# 06_LMS7002M_Power.net
KiCad netlist of a schematic drawn in Altium Designer
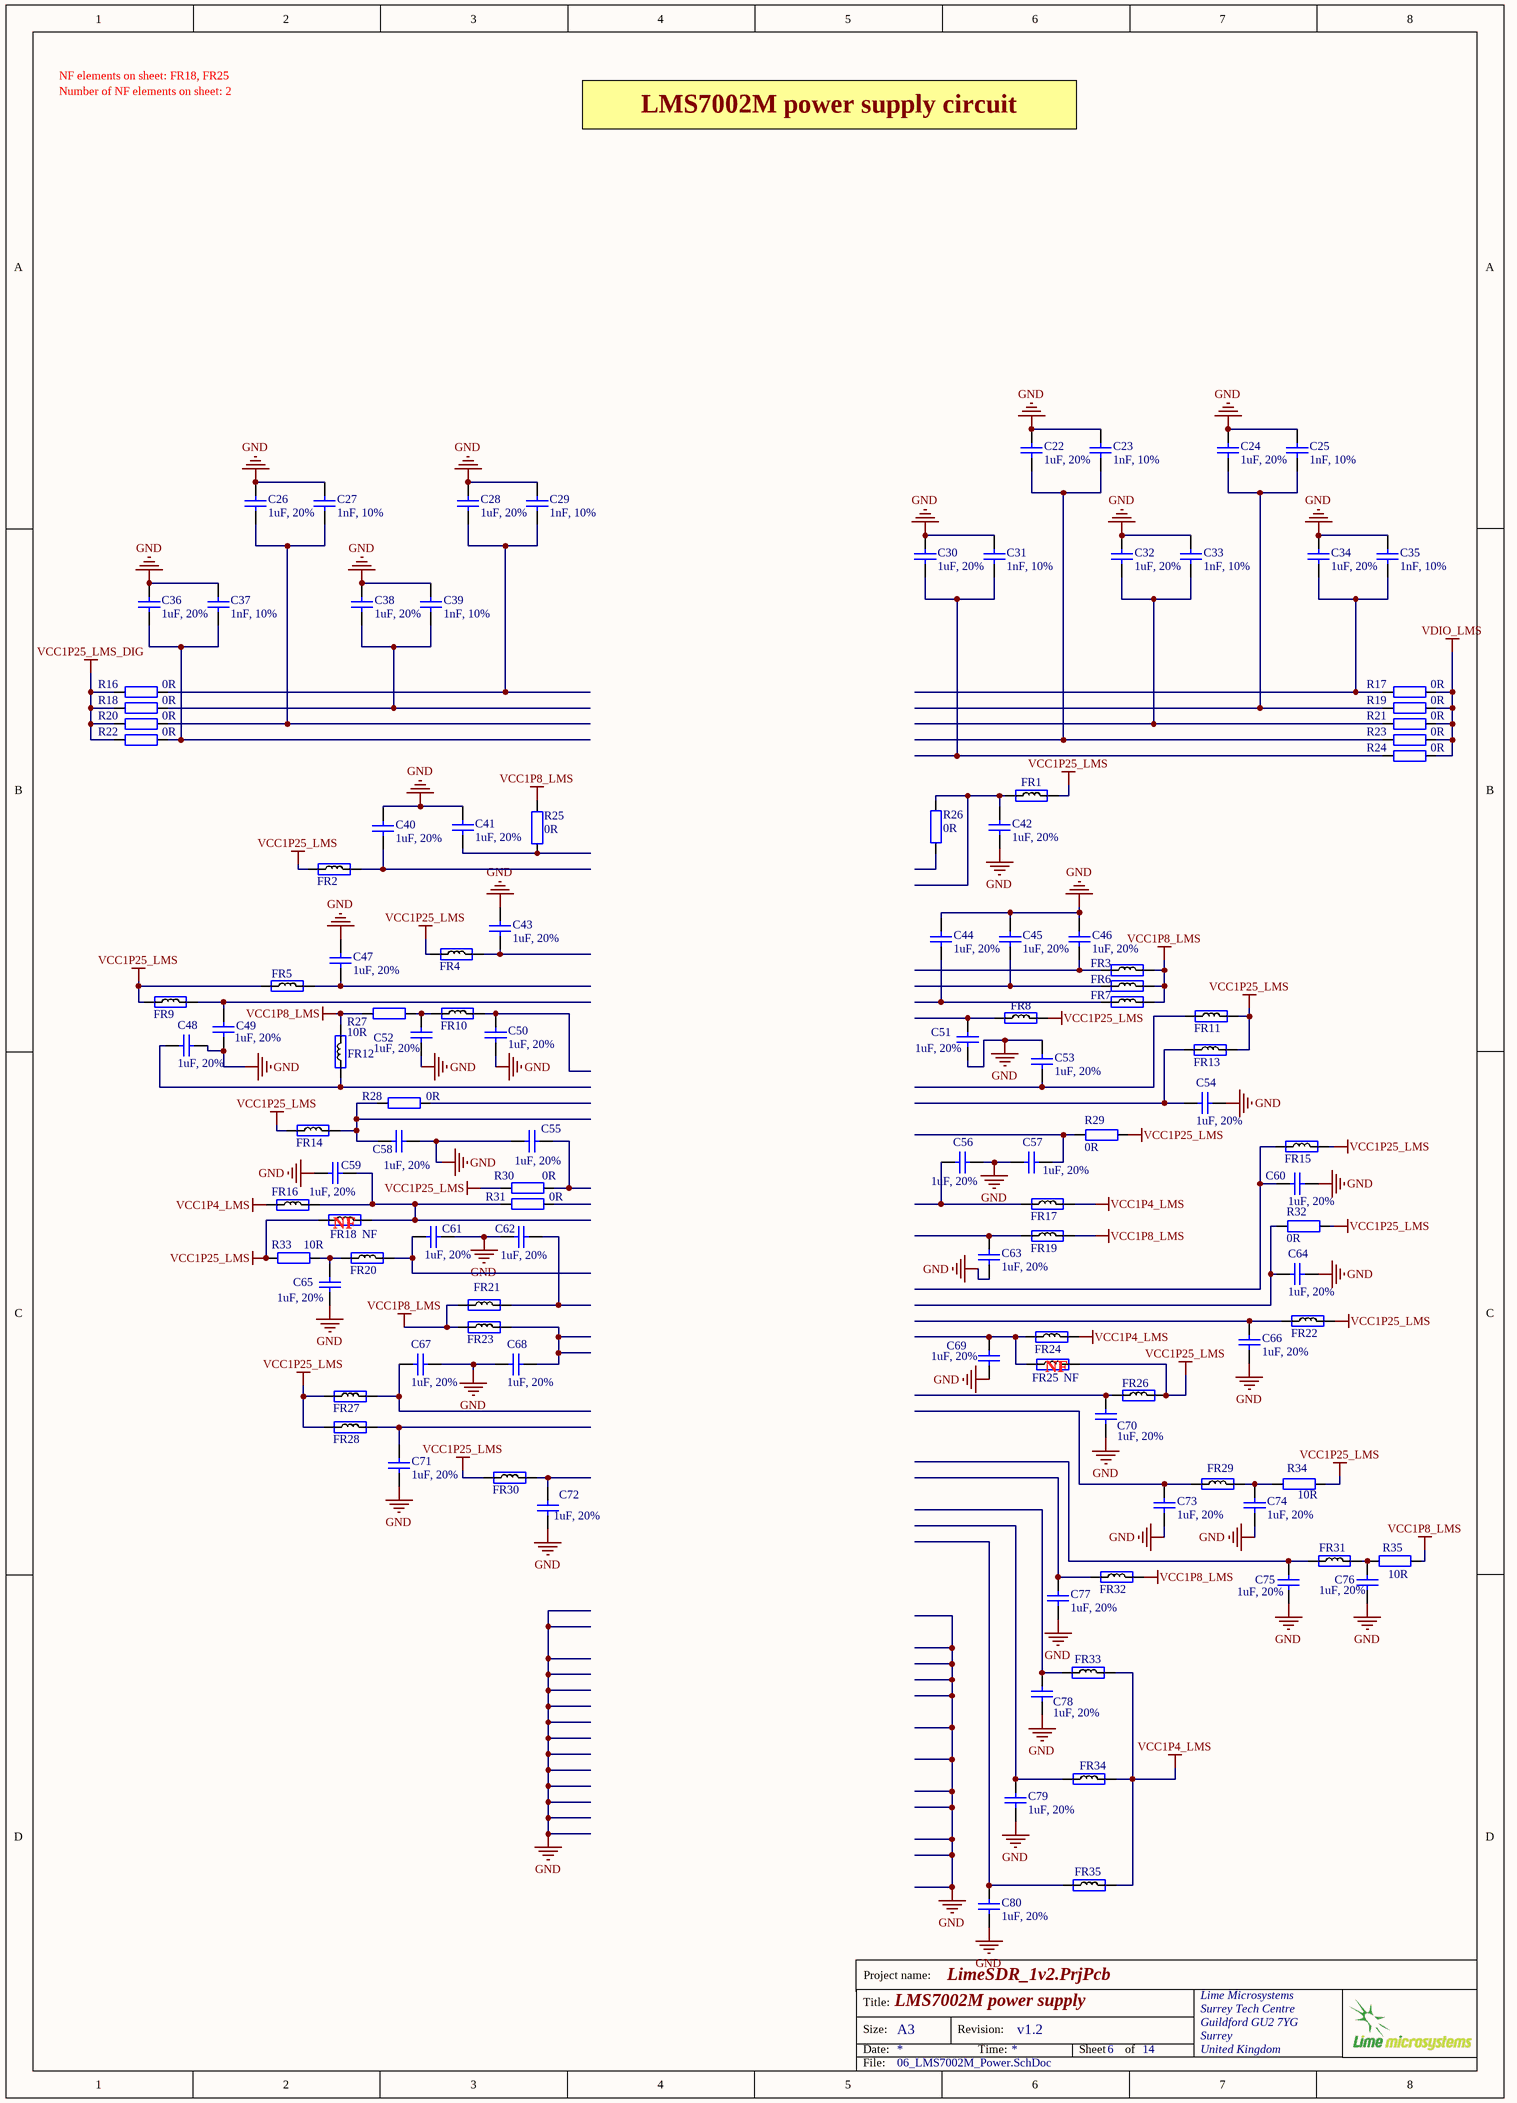
[diagram p0: 06_LMS7002M_Power.SchDoc]

(export (version "E")
  (design (tool "Eeschema 10.0.6"))
  (components
    (comp (ref "C22")
      (value "1uF, 20%")
      (footprint "CAP0201")
      (fields (field (name "TOLERANCE") "±20%") (field (name "MANUFACTURER") "TDK Corporation"))
      (libsource (lib "LimeMicroAltiumLib_schLib") (part "Cap_0402"))
    )
    (comp (ref "C23")
      (value "1nF, 10%")
      (footprint "CAP0201")
      (fields (field (name "TOLERANCE") "±10%") (field (name "MANUFACTURER") "TDK Corporation"))
      (libsource (lib "LimeMicroAltiumLib_schLib") (part "Cap_0402"))
    )
    (comp (ref "C24")
      (value "1uF, 20%")
      (footprint "CAP0201")
      (fields (field (name "TOLERANCE") "±20%") (field (name "MANUFACTURER") "TDK Corporation"))
      (libsource (lib "LimeMicroAltiumLib_schLib") (part "Cap_0402"))
    )
    (comp (ref "C25")
      (value "1nF, 10%")
      (footprint "CAP0201")
      (fields (field (name "TOLERANCE") "±10%") (field (name "MANUFACTURER") "TDK Corporation"))
      (libsource (lib "LimeMicroAltiumLib_schLib") (part "Cap_0402"))
    )
    (comp (ref "C26")
      (value "1uF, 20%")
      (footprint "CAP0201")
      (fields (field (name "TOLERANCE") "±20%") (field (name "MANUFACTURER") "TDK Corporation"))
      (libsource (lib "LimeMicroAltiumLib_schLib") (part "Cap_0402"))
    )
    (comp (ref "C27")
      (value "1nF, 10%")
      (footprint "CAP0201")
      (fields (field (name "TOLERANCE") "±10%") (field (name "MANUFACTURER") "TDK Corporation"))
      (libsource (lib "LimeMicroAltiumLib_schLib") (part "Cap_0402"))
    )
    (comp (ref "C28")
      (value "1uF, 20%")
      (footprint "CAP0201")
      (fields (field (name "TOLERANCE") "±20%") (field (name "MANUFACTURER") "TDK Corporation"))
      (libsource (lib "LimeMicroAltiumLib_schLib") (part "Cap_0402"))
    )
    (comp (ref "C29")
      (value "1nF, 10%")
      (footprint "CAP0201")
      (fields (field (name "TOLERANCE") "±10%") (field (name "MANUFACTURER") "TDK Corporation"))
      (libsource (lib "LimeMicroAltiumLib_schLib") (part "Cap_0402"))
    )
    (comp (ref "C30")
      (value "1uF, 20%")
      (footprint "CAP0201")
      (fields (field (name "TOLERANCE") "±20%") (field (name "MANUFACTURER") "TDK Corporation"))
      (libsource (lib "LimeMicroAltiumLib_schLib") (part "Cap_0402"))
    )
    (comp (ref "C31")
      (value "1nF, 10%")
      (footprint "CAP0201")
      (fields (field (name "TOLERANCE") "±10%") (field (name "MANUFACTURER") "TDK Corporation"))
      (libsource (lib "LimeMicroAltiumLib_schLib") (part "Cap_0402"))
    )
    (comp (ref "C32")
      (value "1uF, 20%")
      (footprint "CAP0201")
      (fields (field (name "TOLERANCE") "±20%") (field (name "MANUFACTURER") "TDK Corporation"))
      (libsource (lib "LimeMicroAltiumLib_schLib") (part "Cap_0402"))
    )
    (comp (ref "C33")
      (value "1nF, 10%")
      (footprint "CAP0201")
      (fields (field (name "TOLERANCE") "±10%") (field (name "MANUFACTURER") "TDK Corporation"))
      (libsource (lib "LimeMicroAltiumLib_schLib") (part "Cap_0402"))
    )
    (comp (ref "C34")
      (value "1uF, 20%")
      (footprint "CAP0201")
      (fields (field (name "TOLERANCE") "±20%") (field (name "MANUFACTURER") "TDK Corporation"))
      (libsource (lib "LimeMicroAltiumLib_schLib") (part "Cap_0402"))
    )
    (comp (ref "C35")
      (value "1nF, 10%")
      (footprint "CAP0201")
      (fields (field (name "TOLERANCE") "±10%") (field (name "MANUFACTURER") "TDK Corporation"))
      (libsource (lib "LimeMicroAltiumLib_schLib") (part "Cap_0402"))
    )
    (comp (ref "C36")
      (value "1uF, 20%")
      (footprint "CAP0201")
      (fields (field (name "TOLERANCE") "±20%") (field (name "MANUFACTURER") "TDK Corporation"))
      (libsource (lib "LimeMicroAltiumLib_schLib") (part "Cap_0402"))
    )
    (comp (ref "C37")
      (value "1nF, 10%")
      (footprint "CAP0201")
      (fields (field (name "TOLERANCE") "±10%") (field (name "MANUFACTURER") "TDK Corporation"))
      (libsource (lib "LimeMicroAltiumLib_schLib") (part "Cap_0402"))
    )
    (comp (ref "C38")
      (value "1uF, 20%")
      (footprint "CAP0201")
      (fields (field (name "TOLERANCE") "±20%") (field (name "MANUFACTURER") "TDK Corporation"))
      (libsource (lib "LimeMicroAltiumLib_schLib") (part "Cap_0402"))
    )
    (comp (ref "C39")
      (value "1nF, 10%")
      (footprint "CAP0201")
      (fields (field (name "TOLERANCE") "±10%") (field (name "MANUFACTURER") "TDK Corporation"))
      (libsource (lib "LimeMicroAltiumLib_schLib") (part "Cap_0402"))
    )
    (comp (ref "C40")
      (value "1uF, 20%")
      (footprint "CAP0201")
      (fields (field (name "TOLERANCE") "±20%") (field (name "MANUFACTURER") "TDK Corporation"))
      (libsource (lib "LimeMicroAltiumLib_schLib") (part "Cap_0402"))
    )
    (comp (ref "C41")
      (value "1uF, 20%")
      (footprint "CAP0201")
      (fields (field (name "TOLERANCE") "±20%") (field (name "MANUFACTURER") "TDK Corporation"))
      (libsource (lib "LimeMicroAltiumLib_schLib") (part "Cap_0402"))
    )
    (comp (ref "C42")
      (value "1uF, 20%")
      (footprint "CAP0201")
      (fields (field (name "TOLERANCE") "±20%") (field (name "MANUFACTURER") "TDK Corporation"))
      (libsource (lib "LimeMicroAltiumLib_schLib") (part "Cap_0402"))
    )
    (comp (ref "C43")
      (value "1uF, 20%")
      (footprint "CAP0201")
      (fields (field (name "TOLERANCE") "±20%") (field (name "MANUFACTURER") "TDK Corporation"))
      (libsource (lib "LimeMicroAltiumLib_schLib") (part "Cap_0402"))
    )
    (comp (ref "C44")
      (value "1uF, 20%")
      (footprint "CAP0201")
      (fields (field (name "TOLERANCE") "±20%") (field (name "MANUFACTURER") "TDK Corporation"))
      (libsource (lib "LimeMicroAltiumLib_schLib") (part "Cap_0402"))
    )
    (comp (ref "C45")
      (value "1uF, 20%")
      (footprint "CAP0201")
      (fields (field (name "TOLERANCE") "±20%") (field (name "MANUFACTURER") "TDK Corporation"))
      (libsource (lib "LimeMicroAltiumLib_schLib") (part "Cap_0402"))
    )
    (comp (ref "C46")
      (value "1uF, 20%")
      (footprint "CAP0201")
      (fields (field (name "TOLERANCE") "±20%") (field (name "MANUFACTURER") "TDK Corporation"))
      (libsource (lib "LimeMicroAltiumLib_schLib") (part "Cap_0402"))
    )
    (comp (ref "C47")
      (value "1uF, 20%")
      (footprint "CAP0201")
      (fields (field (name "TOLERANCE") "±20%") (field (name "MANUFACTURER") "TDK Corporation"))
      (libsource (lib "LimeMicroAltiumLib_schLib") (part "Cap_0402"))
    )
    (comp (ref "C48")
      (value "1uF, 20%")
      (footprint "CAP0201")
      (fields (field (name "TOLERANCE") "±20%") (field (name "MANUFACTURER") "TDK Corporation"))
      (libsource (lib "LimeMicroAltiumLib_schLib") (part "Cap_0402"))
    )
    (comp (ref "C49")
      (value "1uF, 20%")
      (footprint "CAP0201")
      (fields (field (name "TOLERANCE") "±20%") (field (name "MANUFACTURER") "TDK Corporation"))
      (libsource (lib "LimeMicroAltiumLib_schLib") (part "Cap_0402"))
    )
    (comp (ref "C50")
      (value "1uF, 20%")
      (footprint "CAP0201")
      (fields (field (name "TOLERANCE") "±20%") (field (name "MANUFACTURER") "TDK Corporation"))
      (libsource (lib "LimeMicroAltiumLib_schLib") (part "Cap_0402"))
    )
    (comp (ref "C51")
      (value "1uF, 20%")
      (footprint "CAP0201")
      (fields (field (name "TOLERANCE") "±20%") (field (name "MANUFACTURER") "TDK Corporation"))
      (libsource (lib "LimeMicroAltiumLib_schLib") (part "Cap_0402"))
    )
    (comp (ref "C52")
      (value "1uF, 20%")
      (footprint "CAP0201")
      (fields (field (name "TOLERANCE") "±20%") (field (name "MANUFACTURER") "TDK Corporation"))
      (libsource (lib "LimeMicroAltiumLib_schLib") (part "Cap_0402"))
    )
    (comp (ref "C53")
      (value "1uF, 20%")
      (footprint "CAP0201")
      (fields (field (name "TOLERANCE") "±20%") (field (name "MANUFACTURER") "TDK Corporation"))
      (libsource (lib "LimeMicroAltiumLib_schLib") (part "Cap_0402"))
    )
    (comp (ref "C54")
      (value "1uF, 20%")
      (footprint "CAP0201")
      (fields (field (name "TOLERANCE") "±20%") (field (name "MANUFACTURER") "TDK Corporation"))
      (libsource (lib "LimeMicroAltiumLib_schLib") (part "Cap_0402"))
    )
    (comp (ref "C55")
      (value "1uF, 20%")
      (footprint "CAP0201")
      (fields (field (name "TOLERANCE") "±20%") (field (name "MANUFACTURER") "TDK Corporation"))
      (libsource (lib "LimeMicroAltiumLib_schLib") (part "Cap_0402"))
    )
    (comp (ref "C56")
      (value "1uF, 20%")
      (footprint "CAP0201")
      (fields (field (name "TOLERANCE") "±20%") (field (name "MANUFACTURER") "TDK Corporation"))
      (libsource (lib "LimeMicroAltiumLib_schLib") (part "Cap_0402"))
    )
    (comp (ref "C57")
      (value "1uF, 20%")
      (footprint "CAP0201")
      (fields (field (name "TOLERANCE") "±20%") (field (name "MANUFACTURER") "TDK Corporation"))
      (libsource (lib "LimeMicroAltiumLib_schLib") (part "Cap_0402"))
    )
    (comp (ref "C58")
      (value "1uF, 20%")
      (footprint "CAP0201")
      (fields (field (name "TOLERANCE") "±20%") (field (name "MANUFACTURER") "TDK Corporation"))
      (libsource (lib "LimeMicroAltiumLib_schLib") (part "Cap_0402"))
    )
    (comp (ref "C59")
      (value "1uF, 20%")
      (footprint "CAP0201")
      (fields (field (name "TOLERANCE") "±20%") (field (name "MANUFACTURER") "TDK Corporation"))
      (libsource (lib "LimeMicroAltiumLib_schLib") (part "Cap_0402"))
    )
    (comp (ref "C60")
      (value "1uF, 20%")
      (footprint "CAP0201")
      (fields (field (name "TOLERANCE") "±20%") (field (name "MANUFACTURER") "TDK Corporation"))
      (libsource (lib "LimeMicroAltiumLib_schLib") (part "Cap_0402"))
    )
    (comp (ref "C61")
      (value "1uF, 20%")
      (footprint "CAP0201")
      (fields (field (name "TOLERANCE") "±20%") (field (name "MANUFACTURER") "TDK Corporation"))
      (libsource (lib "LimeMicroAltiumLib_schLib") (part "Cap_0402"))
    )
    (comp (ref "C62")
      (value "1uF, 20%")
      (footprint "CAP0201")
      (fields (field (name "TOLERANCE") "±20%") (field (name "MANUFACTURER") "TDK Corporation"))
      (libsource (lib "LimeMicroAltiumLib_schLib") (part "Cap_0402"))
    )
    (comp (ref "C63")
      (value "1uF, 20%")
      (footprint "CAP0201")
      (fields (field (name "TOLERANCE") "±20%") (field (name "MANUFACTURER") "TDK Corporation"))
      (libsource (lib "LimeMicroAltiumLib_schLib") (part "Cap_0402"))
    )
    (comp (ref "C64")
      (value "1uF, 20%")
      (footprint "CAP0201")
      (fields (field (name "TOLERANCE") "±20%") (field (name "MANUFACTURER") "TDK Corporation"))
      (libsource (lib "LimeMicroAltiumLib_schLib") (part "Cap_0402"))
    )
    (comp (ref "C65")
      (value "1uF, 20%")
      (footprint "CAP0201")
      (fields (field (name "TOLERANCE") "±20%") (field (name "MANUFACTURER") "TDK Corporation"))
      (libsource (lib "LimeMicroAltiumLib_schLib") (part "Cap_0402"))
    )
    (comp (ref "C66")
      (value "1uF, 20%")
      (footprint "CAP0201")
      (fields (field (name "TOLERANCE") "±20%") (field (name "MANUFACTURER") "TDK Corporation"))
      (libsource (lib "LimeMicroAltiumLib_schLib") (part "Cap_0402"))
    )
    (comp (ref "C67")
      (value "1uF, 20%")
      (footprint "CAP0201")
      (fields (field (name "TOLERANCE") "±20%") (field (name "MANUFACTURER") "TDK Corporation"))
      (libsource (lib "LimeMicroAltiumLib_schLib") (part "Cap_0402"))
    )
    (comp (ref "C68")
      (value "1uF, 20%")
      (footprint "CAP0201")
      (fields (field (name "TOLERANCE") "±20%") (field (name "MANUFACTURER") "TDK Corporation"))
      (libsource (lib "LimeMicroAltiumLib_schLib") (part "Cap_0402"))
    )
    (comp (ref "C69")
      (value "1uF, 20%")
      (footprint "CAP0201")
      (fields (field (name "TOLERANCE") "±20%") (field (name "MANUFACTURER") "TDK Corporation"))
      (libsource (lib "LimeMicroAltiumLib_schLib") (part "Cap_0402"))
    )
    (comp (ref "C70")
      (value "1uF, 20%")
      (footprint "CAP0201")
      (fields (field (name "TOLERANCE") "±20%") (field (name "MANUFACTURER") "TDK Corporation"))
      (libsource (lib "LimeMicroAltiumLib_schLib") (part "Cap_0402"))
    )
    (comp (ref "C71")
      (value "1uF, 20%")
      (footprint "CAP0201")
      (fields (field (name "TOLERANCE") "±20%") (field (name "MANUFACTURER") "TDK Corporation"))
      (libsource (lib "LimeMicroAltiumLib_schLib") (part "Cap_0402"))
    )
    (comp (ref "C72")
      (value "1uF, 20%")
      (footprint "CAP0201")
      (fields (field (name "TOLERANCE") "±20%") (field (name "MANUFACTURER") "TDK Corporation"))
      (libsource (lib "LimeMicroAltiumLib_schLib") (part "Cap_0402"))
    )
    (comp (ref "C73")
      (value "1uF, 20%")
      (footprint "CAP0201")
      (fields (field (name "TOLERANCE") "±20%") (field (name "MANUFACTURER") "TDK Corporation"))
      (libsource (lib "LimeMicroAltiumLib_schLib") (part "Cap_0402"))
    )
    (comp (ref "C74")
      (value "1uF, 20%")
      (footprint "CAP0201")
      (fields (field (name "TOLERANCE") "±20%") (field (name "MANUFACTURER") "TDK Corporation"))
      (libsource (lib "LimeMicroAltiumLib_schLib") (part "Cap_0402"))
    )
    (comp (ref "C75")
      (value "1uF, 20%")
      (footprint "CAP0201")
      (fields (field (name "TOLERANCE") "±20%") (field (name "MANUFACTURER") "TDK Corporation"))
      (libsource (lib "LimeMicroAltiumLib_schLib") (part "Cap_0402"))
    )
    (comp (ref "C76")
      (value "1uF, 20%")
      (footprint "CAP0201")
      (fields (field (name "TOLERANCE") "±20%") (field (name "MANUFACTURER") "TDK Corporation"))
      (libsource (lib "LimeMicroAltiumLib_schLib") (part "Cap_0402"))
    )
    (comp (ref "C77")
      (value "1uF, 20%")
      (footprint "CAP0201")
      (fields (field (name "TOLERANCE") "±20%") (field (name "MANUFACTURER") "TDK Corporation"))
      (libsource (lib "LimeMicroAltiumLib_schLib") (part "Cap_0402"))
    )
    (comp (ref "C78")
      (value "1uF, 20%")
      (footprint "CAP0201")
      (fields (field (name "TOLERANCE") "±20%") (field (name "MANUFACTURER") "TDK Corporation"))
      (libsource (lib "LimeMicroAltiumLib_schLib") (part "Cap_0402"))
    )
    (comp (ref "C79")
      (value "1uF, 20%")
      (footprint "CAP0201")
      (fields (field (name "TOLERANCE") "±20%") (field (name "MANUFACTURER") "TDK Corporation"))
      (libsource (lib "LimeMicroAltiumLib_schLib") (part "Cap_0402"))
    )
    (comp (ref "C80")
      (value "1uF, 20%")
      (footprint "CAP0201")
      (fields (field (name "TOLERANCE") "±20%") (field (name "MANUFACTURER") "TDK Corporation"))
      (libsource (lib "LimeMicroAltiumLib_schLib") (part "Cap_0402"))
    )
    (comp (ref "FR1")
      (value "Ferrite")
      (footprint "RES0201")
      (fields (field (name "MANUFACTURER") "Taiyo Yuden"))
      (libsource (lib "LimeMicroAltiumLib_schLib") (part "Ferrite"))
    )
    (comp (ref "FR2")
      (value "Ferrite")
      (footprint "RES0201")
      (fields (field (name "MANUFACTURER") "Taiyo Yuden"))
      (libsource (lib "LimeMicroAltiumLib_schLib") (part "Ferrite"))
    )
    (comp (ref "FR3")
      (value "Ferrite")
      (footprint "RES0201")
      (fields (field (name "MANUFACTURER") "Taiyo Yuden"))
      (libsource (lib "LimeMicroAltiumLib_schLib") (part "Ferrite"))
    )
    (comp (ref "FR4")
      (value "Ferrite")
      (footprint "RES0201")
      (fields (field (name "MANUFACTURER") "Taiyo Yuden"))
      (libsource (lib "LimeMicroAltiumLib_schLib") (part "Ferrite"))
    )
    (comp (ref "FR5")
      (value "Ferrite")
      (footprint "RES0201")
      (fields (field (name "MANUFACTURER") "Taiyo Yuden"))
      (libsource (lib "LimeMicroAltiumLib_schLib") (part "Ferrite"))
    )
    (comp (ref "FR6")
      (value "Ferrite")
      (footprint "RES0201")
      (fields (field (name "MANUFACTURER") "Taiyo Yuden"))
      (libsource (lib "LimeMicroAltiumLib_schLib") (part "Ferrite"))
    )
    (comp (ref "FR7")
      (value "Ferrite")
      (footprint "RES0201")
      (fields (field (name "MANUFACTURER") "Taiyo Yuden"))
      (libsource (lib "LimeMicroAltiumLib_schLib") (part "Ferrite"))
    )
    (comp (ref "FR8")
      (value "Ferrite")
      (footprint "RES0201")
      (fields (field (name "MANUFACTURER") "Taiyo Yuden"))
      (libsource (lib "LimeMicroAltiumLib_schLib") (part "Ferrite"))
    )
    (comp (ref "FR9")
      (value "Ferrite")
      (footprint "RES0201")
      (fields (field (name "MANUFACTURER") "Taiyo Yuden"))
      (libsource (lib "LimeMicroAltiumLib_schLib") (part "Ferrite"))
    )
    (comp (ref "FR10")
      (value "Ferrite")
      (footprint "RES0201")
      (fields (field (name "MANUFACTURER") "Taiyo Yuden"))
      (libsource (lib "LimeMicroAltiumLib_schLib") (part "Ferrite"))
    )
    (comp (ref "FR11")
      (value "Ferrite")
      (footprint "RES0201")
      (fields (field (name "MANUFACTURER") "Taiyo Yuden"))
      (libsource (lib "LimeMicroAltiumLib_schLib") (part "Ferrite"))
    )
    (comp (ref "FR12")
      (value "Ferrite")
      (footprint "RES0201")
      (fields (field (name "MANUFACTURER") "Taiyo Yuden"))
      (libsource (lib "LimeMicroAltiumLib_schLib") (part "Ferrite"))
    )
    (comp (ref "FR13")
      (value "Ferrite")
      (footprint "RES0201")
      (fields (field (name "MANUFACTURER") "Taiyo Yuden"))
      (libsource (lib "LimeMicroAltiumLib_schLib") (part "Ferrite"))
    )
    (comp (ref "FR14")
      (value "Ferrite")
      (footprint "RES0201")
      (fields (field (name "MANUFACTURER") "Taiyo Yuden"))
      (libsource (lib "LimeMicroAltiumLib_schLib") (part "Ferrite"))
    )
    (comp (ref "FR15")
      (value "Ferrite")
      (footprint "RES0201")
      (fields (field (name "MANUFACTURER") "Taiyo Yuden"))
      (libsource (lib "LimeMicroAltiumLib_schLib") (part "Ferrite"))
    )
    (comp (ref "FR16")
      (value "Ferrite")
      (footprint "RES0201")
      (fields (field (name "MANUFACTURER") "Taiyo Yuden"))
      (libsource (lib "LimeMicroAltiumLib_schLib") (part "Ferrite"))
    )
    (comp (ref "FR17")
      (value "Ferrite")
      (footprint "RES0201")
      (fields (field (name "MANUFACTURER") "Taiyo Yuden"))
      (libsource (lib "LimeMicroAltiumLib_schLib") (part "Ferrite"))
    )
    (comp (ref "FR18")
      (value "Ferrite")
      (footprint "RES0201")
      (fields (field (name "MANUFACTURER") "Taiyo Yuden") (field (name "ASSEMBLY INFO") "NF"))
      (libsource (lib "LimeMicroAltiumLib_schLib") (part "Ferrite"))
    )
    (comp (ref "FR19")
      (value "Ferrite")
      (footprint "RES0201")
      (fields (field (name "MANUFACTURER") "Taiyo Yuden"))
      (libsource (lib "LimeMicroAltiumLib_schLib") (part "Ferrite"))
    )
    (comp (ref "FR20")
      (value "Ferrite")
      (footprint "RES0201")
      (fields (field (name "MANUFACTURER") "Taiyo Yuden"))
      (libsource (lib "LimeMicroAltiumLib_schLib") (part "Ferrite"))
    )
    (comp (ref "FR21")
      (value "Ferrite")
      (footprint "RES0201")
      (fields (field (name "MANUFACTURER") "Taiyo Yuden"))
      (libsource (lib "LimeMicroAltiumLib_schLib") (part "Ferrite"))
    )
    (comp (ref "FR22")
      (value "Ferrite")
      (footprint "RES0201")
      (fields (field (name "MANUFACTURER") "Taiyo Yuden"))
      (libsource (lib "LimeMicroAltiumLib_schLib") (part "Ferrite"))
    )
    (comp (ref "FR23")
      (value "Ferrite")
      (footprint "RES0201")
      (fields (field (name "MANUFACTURER") "Taiyo Yuden"))
      (libsource (lib "LimeMicroAltiumLib_schLib") (part "Ferrite"))
    )
    (comp (ref "FR24")
      (value "Ferrite")
      (footprint "RES0201")
      (fields (field (name "MANUFACTURER") "Taiyo Yuden"))
      (libsource (lib "LimeMicroAltiumLib_schLib") (part "Ferrite"))
    )
    (comp (ref "FR25")
      (value "Ferrite")
      (footprint "RES0201")
      (fields (field (name "MANUFACTURER") "Taiyo Yuden") (field (name "ASSEMBLY INFO") "NF"))
      (libsource (lib "LimeMicroAltiumLib_schLib") (part "Ferrite"))
    )
    (comp (ref "FR26")
      (value "Ferrite")
      (footprint "RES0201")
      (fields (field (name "MANUFACTURER") "Taiyo Yuden"))
      (libsource (lib "LimeMicroAltiumLib_schLib") (part "Ferrite"))
    )
    (comp (ref "FR27")
      (value "Ferrite")
      (footprint "RES0201")
      (fields (field (name "MANUFACTURER") "Taiyo Yuden"))
      (libsource (lib "LimeMicroAltiumLib_schLib") (part "Ferrite"))
    )
    (comp (ref "FR28")
      (value "Ferrite")
      (footprint "RES0201")
      (fields (field (name "MANUFACTURER") "Taiyo Yuden"))
      (libsource (lib "LimeMicroAltiumLib_schLib") (part "Ferrite"))
    )
    (comp (ref "FR29")
      (value "Ferrite")
      (footprint "RES0201")
      (fields (field (name "MANUFACTURER") "Taiyo Yuden"))
      (libsource (lib "LimeMicroAltiumLib_schLib") (part "Ferrite"))
    )
    (comp (ref "FR30")
      (value "Ferrite")
      (footprint "RES0201")
      (fields (field (name "MANUFACTURER") "Taiyo Yuden"))
      (libsource (lib "LimeMicroAltiumLib_schLib") (part "Ferrite"))
    )
    (comp (ref "FR31")
      (value "Ferrite")
      (footprint "RES0201")
      (fields (field (name "MANUFACTURER") "Taiyo Yuden"))
      (libsource (lib "LimeMicroAltiumLib_schLib") (part "Ferrite"))
    )
    (comp (ref "FR32")
      (value "Ferrite")
      (footprint "RES0201")
      (fields (field (name "MANUFACTURER") "Taiyo Yuden"))
      (libsource (lib "LimeMicroAltiumLib_schLib") (part "Ferrite"))
    )
    (comp (ref "FR33")
      (value "Ferrite")
      (footprint "RES0201")
      (fields (field (name "MANUFACTURER") "Taiyo Yuden"))
      (libsource (lib "LimeMicroAltiumLib_schLib") (part "Ferrite"))
    )
    (comp (ref "FR34")
      (value "Ferrite")
      (footprint "RES0201")
      (fields (field (name "MANUFACTURER") "Taiyo Yuden"))
      (libsource (lib "LimeMicroAltiumLib_schLib") (part "Ferrite"))
    )
    (comp (ref "FR35")
      (value "Ferrite")
      (footprint "RES0201")
      (fields (field (name "MANUFACTURER") "Taiyo Yuden"))
      (libsource (lib "LimeMicroAltiumLib_schLib") (part "Ferrite"))
    )
    (comp (ref "R16")
      (value "0R")
      (footprint "RES0402")
      (fields (field (name "MANUFACTURER") "Yageo") (field (name "TOLERANCE") "Jumper"))
      (libsource (lib "LimeMicroAltiumLib_schLib") (part "Res_0402"))
    )
    (comp (ref "R17")
      (value "0R")
      (footprint "RES0402")
      (fields (field (name "MANUFACTURER") "Yageo") (field (name "TOLERANCE") "Jumper"))
      (libsource (lib "LimeMicroAltiumLib_schLib") (part "Res_0402"))
    )
    (comp (ref "R18")
      (value "0R")
      (footprint "RES0402")
      (fields (field (name "MANUFACTURER") "Yageo") (field (name "TOLERANCE") "Jumper"))
      (libsource (lib "LimeMicroAltiumLib_schLib") (part "Res_0402"))
    )
    (comp (ref "R19")
      (value "0R")
      (footprint "RES0402")
      (fields (field (name "MANUFACTURER") "Yageo") (field (name "TOLERANCE") "Jumper"))
      (libsource (lib "LimeMicroAltiumLib_schLib") (part "Res_0402"))
    )
    (comp (ref "R20")
      (value "0R")
      (footprint "RES0402")
      (fields (field (name "MANUFACTURER") "Yageo") (field (name "TOLERANCE") "Jumper"))
      (libsource (lib "LimeMicroAltiumLib_schLib") (part "Res_0402"))
    )
    (comp (ref "R21")
      (value "0R")
      (footprint "RES0402")
      (fields (field (name "MANUFACTURER") "Yageo") (field (name "TOLERANCE") "Jumper"))
      (libsource (lib "LimeMicroAltiumLib_schLib") (part "Res_0402"))
    )
    (comp (ref "R22")
      (value "0R")
      (footprint "RES0402")
      (fields (field (name "MANUFACTURER") "Yageo") (field (name "TOLERANCE") "Jumper"))
      (libsource (lib "LimeMicroAltiumLib_schLib") (part "Res_0402"))
    )
    (comp (ref "R23")
      (value "0R")
      (footprint "RES0402")
      (fields (field (name "MANUFACTURER") "Yageo") (field (name "TOLERANCE") "Jumper"))
      (libsource (lib "LimeMicroAltiumLib_schLib") (part "Res_0402"))
    )
    (comp (ref "R24")
      (value "0R")
      (footprint "RES0402")
      (fields (field (name "MANUFACTURER") "Yageo") (field (name "TOLERANCE") "Jumper"))
      (libsource (lib "LimeMicroAltiumLib_schLib") (part "Res_0402"))
    )
    (comp (ref "R25")
      (value "0R")
      (footprint "RES0201")
      (fields (field (name "MANUFACTURER") "Rohm Semiconductor") (field (name "TOLERANCE") "Jumper"))
      (libsource (lib "LimeMicroAltiumLib_schLib") (part "Res_0402"))
    )
    (comp (ref "R26")
      (value "0R")
      (footprint "RES0201")
      (fields (field (name "MANUFACTURER") "Rohm Semiconductor") (field (name "TOLERANCE") "Jumper"))
      (libsource (lib "LimeMicroAltiumLib_schLib") (part "Res_0402"))
    )
    (comp (ref "R27")
      (value "10R")
      (footprint "RES0201")
      (fields
        (field (name "MANUFACTURER") "Panasonic Electronic Components")
        (field (name "TOLERANCE") "±1%")
        (field (name "MANUFACTURER PART NUMBER") "ERJ-1GEF10R0C")
      )
      (libsource (lib "LimeMicroAltiumLib_schLib") (part "Res_0402"))
    )
    (comp (ref "R28")
      (value "0R")
      (footprint "RES0201")
      (fields (field (name "MANUFACTURER") "Rohm Semiconductor") (field (name "TOLERANCE") "Jumper"))
      (libsource (lib "LimeMicroAltiumLib_schLib") (part "Res_0402"))
    )
    (comp (ref "R29")
      (value "0R")
      (footprint "RES0201")
      (fields (field (name "MANUFACTURER") "Rohm Semiconductor") (field (name "TOLERANCE") "Jumper"))
      (libsource (lib "LimeMicroAltiumLib_schLib") (part "Res_0402"))
    )
    (comp (ref "R30")
      (value "0R")
      (footprint "RES0201")
      (fields (field (name "MANUFACTURER") "Rohm Semiconductor") (field (name "TOLERANCE") "Jumper"))
      (libsource (lib "LimeMicroAltiumLib_schLib") (part "Res_0402"))
    )
    (comp (ref "R31")
      (value "0R")
      (footprint "RES0201")
      (fields (field (name "MANUFACTURER") "Rohm Semiconductor") (field (name "TOLERANCE") "Jumper"))
      (libsource (lib "LimeMicroAltiumLib_schLib") (part "Res_0402"))
    )
    (comp (ref "R32")
      (value "0R")
      (footprint "RES0201")
      (fields (field (name "MANUFACTURER") "Rohm Semiconductor") (field (name "TOLERANCE") "Jumper"))
      (libsource (lib "LimeMicroAltiumLib_schLib") (part "Res_0402"))
    )
    (comp (ref "R33")
      (value "10R")
      (footprint "RES0201")
      (fields
        (field (name "MANUFACTURER") "Panasonic Electronic Components")
        (field (name "TOLERANCE") "±1%")
        (field (name "MANUFACTURER PART NUMBER") "ERJ-1GEF10R0C")
      )
      (libsource (lib "LimeMicroAltiumLib_schLib") (part "Res_0402"))
    )
    (comp (ref "R34")
      (value "10R")
      (footprint "RES0201")
      (fields
        (field (name "MANUFACTURER") "Panasonic Electronic Components")
        (field (name "TOLERANCE") "±1%")
        (field (name "MANUFACTURER PART NUMBER") "ERJ-1GEF10R0C")
      )
      (libsource (lib "LimeMicroAltiumLib_schLib") (part "Res_0402"))
    )
    (comp (ref "R35")
      (value "10R")
      (footprint "RES0201")
      (fields
        (field (name "MANUFACTURER") "Panasonic Electronic Components")
        (field (name "TOLERANCE") "±1%")
        (field (name "MANUFACTURER PART NUMBER") "ERJ-1GEF10R0C")
      )
      (libsource (lib "LimeMicroAltiumLib_schLib") (part "Res_0402"))
    )
  )
  (nets
    (net (code "1") (name "GND") (class "Default")
      (node (ref "C22") (pin "2") (pinfunction "2_2") (pintype "passive"))
      (node (ref "C23") (pin "2") (pinfunction "2_2") (pintype "passive"))
      (node (ref "C24") (pin "2") (pinfunction "2_2") (pintype "passive"))
      (node (ref "C25") (pin "2") (pinfunction "2_2") (pintype "passive"))
      (node (ref "C26") (pin "2") (pinfunction "2_2") (pintype "passive"))
      (node (ref "C27") (pin "2") (pinfunction "2_2") (pintype "passive"))
      (node (ref "C28") (pin "2") (pinfunction "2_2") (pintype "passive"))
      (node (ref "C29") (pin "2") (pinfunction "2_2") (pintype "passive"))
      (node (ref "C30") (pin "2") (pinfunction "2_2") (pintype "passive"))
      (node (ref "C31") (pin "2") (pinfunction "2_2") (pintype "passive"))
      (node (ref "C32") (pin "2") (pinfunction "2_2") (pintype "passive"))
      (node (ref "C33") (pin "2") (pinfunction "2_2") (pintype "passive"))
      (node (ref "C34") (pin "2") (pinfunction "2_2") (pintype "passive"))
      (node (ref "C35") (pin "2") (pinfunction "2_2") (pintype "passive"))
      (node (ref "C36") (pin "2") (pinfunction "2_2") (pintype "passive"))
      (node (ref "C37") (pin "2") (pinfunction "2_2") (pintype "passive"))
      (node (ref "C38") (pin "2") (pinfunction "2_2") (pintype "passive"))
      (node (ref "C39") (pin "2") (pinfunction "2_2") (pintype "passive"))
      (node (ref "C40") (pin "2") (pinfunction "2_2") (pintype "passive"))
      (node (ref "C41") (pin "2") (pinfunction "2_2") (pintype "passive"))
      (node (ref "C42") (pin "2") (pinfunction "2_2") (pintype "passive"))
      (node (ref "C43") (pin "2") (pinfunction "2_2") (pintype "passive"))
      (node (ref "C44") (pin "2") (pinfunction "2_2") (pintype "passive"))
      (node (ref "C45") (pin "2") (pinfunction "2_2") (pintype "passive"))
      (node (ref "C46") (pin "2") (pinfunction "2_2") (pintype "passive"))
      (node (ref "C47") (pin "2") (pinfunction "2_2") (pintype "passive"))
      (node (ref "C48") (pin "2") (pinfunction "2_2") (pintype "passive"))
      (node (ref "C49") (pin "2") (pinfunction "2_2") (pintype "passive"))
      (node (ref "C50") (pin "2") (pinfunction "2_2") (pintype "passive"))
      (node (ref "C51") (pin "2") (pinfunction "2_2") (pintype "passive"))
      (node (ref "C52") (pin "2") (pinfunction "2_2") (pintype "passive"))
      (node (ref "C53") (pin "2") (pinfunction "2_2") (pintype "passive"))
      (node (ref "C54") (pin "2") (pinfunction "2_2") (pintype "passive"))
      (node (ref "C55") (pin "2") (pinfunction "2_2") (pintype "passive"))
      (node (ref "C56") (pin "2") (pinfunction "2_2") (pintype "passive"))
      (node (ref "C57") (pin "2") (pinfunction "2_2") (pintype "passive"))
      (node (ref "C58") (pin "1") (pinfunction "1_1") (pintype "passive"))
      (node (ref "C59") (pin "2") (pinfunction "2_2") (pintype "passive"))
      (node (ref "C60") (pin "2") (pinfunction "2_2") (pintype "passive"))
      (node (ref "C61") (pin "2") (pinfunction "2_2") (pintype "passive"))
      (node (ref "C62") (pin "2") (pinfunction "2_2") (pintype "passive"))
      (node (ref "C63") (pin "2") (pinfunction "2_2") (pintype "passive"))
      (node (ref "C64") (pin "2") (pinfunction "2_2") (pintype "passive"))
      (node (ref "C65") (pin "2") (pinfunction "2_2") (pintype "passive"))
      (node (ref "C66") (pin "2") (pinfunction "2_2") (pintype "passive"))
      (node (ref "C67") (pin "2") (pinfunction "2_2") (pintype "passive"))
      (node (ref "C68") (pin "2") (pinfunction "2_2") (pintype "passive"))
      (node (ref "C69") (pin "2") (pinfunction "2_2") (pintype "passive"))
      (node (ref "C70") (pin "2") (pinfunction "2_2") (pintype "passive"))
      (node (ref "C71") (pin "2") (pinfunction "2_2") (pintype "passive"))
      (node (ref "C72") (pin "2") (pinfunction "2_2") (pintype "passive"))
      (node (ref "C73") (pin "2") (pinfunction "2_2") (pintype "passive"))
      (node (ref "C74") (pin "2") (pinfunction "2_2") (pintype "passive"))
      (node (ref "C75") (pin "2") (pinfunction "2_2") (pintype "passive"))
      (node (ref "C76") (pin "2") (pinfunction "2_2") (pintype "passive"))
      (node (ref "C77") (pin "2") (pinfunction "2_2") (pintype "passive"))
      (node (ref "C78") (pin "2") (pinfunction "2_2") (pintype "passive"))
      (node (ref "C79") (pin "2") (pinfunction "2_2") (pintype "passive"))
      (node (ref "C80") (pin "2") (pinfunction "2_2") (pintype "passive"))
    )
    (net (code "2") (name "Net-(C22-Pad1)") (class "Default")
      (node (ref "C22") (pin "1") (pinfunction "1_1") (pintype "passive"))
      (node (ref "C23") (pin "1") (pinfunction "1_1") (pintype "passive"))
      (node (ref "R23") (pin "2") (pinfunction "2_2") (pintype "passive"))
    )
    (net (code "3") (name "Net-(C24-Pad1)") (class "Default")
      (node (ref "C24") (pin "1") (pinfunction "1_1") (pintype "passive"))
      (node (ref "C25") (pin "1") (pinfunction "1_1") (pintype "passive"))
      (node (ref "R19") (pin "2") (pinfunction "2_2") (pintype "passive"))
    )
    (net (code "4") (name "Net-(C26-Pad1)") (class "Default")
      (node (ref "C26") (pin "1") (pinfunction "1_1") (pintype "passive"))
      (node (ref "C27") (pin "1") (pinfunction "1_1") (pintype "passive"))
      (node (ref "R20") (pin "1") (pinfunction "1_1") (pintype "passive"))
    )
    (net (code "5") (name "Net-(C28-Pad1)") (class "Default")
      (node (ref "C28") (pin "1") (pinfunction "1_1") (pintype "passive"))
      (node (ref "C29") (pin "1") (pinfunction "1_1") (pintype "passive"))
      (node (ref "R16") (pin "1") (pinfunction "1_1") (pintype "passive"))
    )
    (net (code "6") (name "Net-(C30-Pad1)") (class "Default")
      (node (ref "C30") (pin "1") (pinfunction "1_1") (pintype "passive"))
      (node (ref "C31") (pin "1") (pinfunction "1_1") (pintype "passive"))
      (node (ref "R24") (pin "2") (pinfunction "2_2") (pintype "passive"))
    )
    (net (code "7") (name "Net-(C32-Pad1)") (class "Default")
      (node (ref "C32") (pin "1") (pinfunction "1_1") (pintype "passive"))
      (node (ref "C33") (pin "1") (pinfunction "1_1") (pintype "passive"))
      (node (ref "R21") (pin "2") (pinfunction "2_2") (pintype "passive"))
    )
    (net (code "8") (name "Net-(C34-Pad1)") (class "Default")
      (node (ref "C34") (pin "1") (pinfunction "1_1") (pintype "passive"))
      (node (ref "C35") (pin "1") (pinfunction "1_1") (pintype "passive"))
      (node (ref "R17") (pin "2") (pinfunction "2_2") (pintype "passive"))
    )
    (net (code "9") (name "Net-(C36-Pad1)") (class "Default")
      (node (ref "C36") (pin "1") (pinfunction "1_1") (pintype "passive"))
      (node (ref "C37") (pin "1") (pinfunction "1_1") (pintype "passive"))
      (node (ref "R22") (pin "1") (pinfunction "1_1") (pintype "passive"))
    )
    (net (code "10") (name "Net-(C38-Pad1)") (class "Default")
      (node (ref "C38") (pin "1") (pinfunction "1_1") (pintype "passive"))
      (node (ref "C39") (pin "1") (pinfunction "1_1") (pintype "passive"))
      (node (ref "R18") (pin "1") (pinfunction "1_1") (pintype "passive"))
    )
    (net (code "11") (name "Net-(C40-Pad1)") (class "Default")
      (node (ref "C40") (pin "1") (pinfunction "1_1") (pintype "passive"))
      (node (ref "FR2") (pin "2") (pinfunction "2_2") (pintype "passive"))
    )
    (net (code "12") (name "Net-(C41-Pad1)") (class "Default")
      (node (ref "C41") (pin "1") (pinfunction "1_1") (pintype "passive"))
      (node (ref "R25") (pin "1") (pinfunction "1_1") (pintype "passive"))
    )
    (net (code "13") (name "Net-(C42-Pad1)") (class "Default")
      (node (ref "C42") (pin "1") (pinfunction "1_1") (pintype "passive"))
      (node (ref "FR1") (pin "1") (pinfunction "1_1") (pintype "passive"))
      (node (ref "R26") (pin "1") (pinfunction "1_1") (pintype "passive"))
    )
    (net (code "14") (name "Net-(C43-Pad1)") (class "Default")
      (node (ref "C43") (pin "1") (pinfunction "1_1") (pintype "passive"))
      (node (ref "FR4") (pin "2") (pinfunction "2_2") (pintype "passive"))
    )
    (net (code "15") (name "Net-(C44-Pad1)") (class "Default")
      (node (ref "C44") (pin "1") (pinfunction "1_1") (pintype "passive"))
      (node (ref "FR7") (pin "1") (pinfunction "1_1") (pintype "passive"))
    )
    (net (code "16") (name "Net-(C45-Pad1)") (class "Default")
      (node (ref "C45") (pin "1") (pinfunction "1_1") (pintype "passive"))
      (node (ref "FR6") (pin "1") (pinfunction "1_1") (pintype "passive"))
    )
    (net (code "17") (name "Net-(C46-Pad1)") (class "Default")
      (node (ref "C46") (pin "1") (pinfunction "1_1") (pintype "passive"))
      (node (ref "FR3") (pin "1") (pinfunction "1_1") (pintype "passive"))
    )
    (net (code "18") (name "Net-(C47-Pad1)") (class "Default")
      (node (ref "C47") (pin "1") (pinfunction "1_1") (pintype "passive"))
      (node (ref "FR5") (pin "2") (pinfunction "2_2") (pintype "passive"))
    )
    (net (code "19") (name "Net-(C48-Pad1)") (class "Default")
      (node (ref "C48") (pin "1") (pinfunction "1_1") (pintype "passive"))
      (node (ref "FR12") (pin "1") (pinfunction "1_1") (pintype "passive"))
    )
    (net (code "20") (name "Net-(C49-Pad1)") (class "Default")
      (node (ref "C49") (pin "1") (pinfunction "1_1") (pintype "passive"))
      (node (ref "FR9") (pin "2") (pinfunction "2_2") (pintype "passive"))
    )
    (net (code "21") (name "Net-(C50-Pad1)") (class "Default")
      (node (ref "C50") (pin "1") (pinfunction "1_1") (pintype "passive"))
      (node (ref "FR10") (pin "2") (pinfunction "2_2") (pintype "passive"))
    )
    (net (code "22") (name "Net-(C51-Pad1)") (class "Default")
      (node (ref "C51") (pin "1") (pinfunction "1_1") (pintype "passive"))
      (node (ref "FR8") (pin "1") (pinfunction "1_1") (pintype "passive"))
    )
    (net (code "23") (name "Net-(C52-Pad1)") (class "Default")
      (node (ref "C52") (pin "1") (pinfunction "1_1") (pintype "passive"))
      (node (ref "FR10") (pin "1") (pinfunction "1_1") (pintype "passive"))
      (node (ref "R27") (pin "1") (pinfunction "1_1") (pintype "passive"))
    )
    (net (code "24") (name "Net-(C53-Pad1)") (class "Default")
      (node (ref "C53") (pin "1") (pinfunction "1_1") (pintype "passive"))
      (node (ref "FR11") (pin "1") (pinfunction "1_1") (pintype "passive"))
    )
    (net (code "25") (name "Net-(C54-Pad1)") (class "Default")
      (node (ref "C54") (pin "1") (pinfunction "1_1") (pintype "passive"))
      (node (ref "FR13") (pin "1") (pinfunction "1_1") (pintype "passive"))
    )
    (net (code "26") (name "Net-(C55-Pad1)") (class "Default")
      (node (ref "C55") (pin "1") (pinfunction "1_1") (pintype "passive"))
      (node (ref "R30") (pin "1") (pinfunction "1_1") (pintype "passive"))
    )
    (net (code "27") (name "Net-(C56-Pad1)") (class "Default")
      (node (ref "C56") (pin "1") (pinfunction "1_1") (pintype "passive"))
      (node (ref "FR17") (pin "1") (pinfunction "1_1") (pintype "passive"))
    )
    (net (code "28") (name "Net-(C57-Pad1)") (class "Default")
      (node (ref "C57") (pin "1") (pinfunction "1_1") (pintype "passive"))
      (node (ref "R29") (pin "2") (pinfunction "2_2") (pintype "passive"))
    )
    (net (code "29") (name "Net-(C58-Pad2)") (class "Default")
      (node (ref "C58") (pin "2") (pinfunction "2_2") (pintype "passive"))
      (node (ref "FR14") (pin "2") (pinfunction "2_2") (pintype "passive"))
      (node (ref "R28") (pin "2") (pinfunction "2_2") (pintype "passive"))
    )
    (net (code "30") (name "Net-(C59-Pad1)") (class "Default")
      (node (ref "C59") (pin "1") (pinfunction "1_1") (pintype "passive"))
      (node (ref "FR16") (pin "2") (pinfunction "2_2") (pintype "passive"))
      (node (ref "FR18") (pin "2") (pinfunction "2_2") (pintype "passive"))
      (node (ref "R31") (pin "2") (pinfunction "2_2") (pintype "passive"))
    )
    (net (code "31") (name "Net-(C60-Pad1)") (class "Default")
      (node (ref "C60") (pin "1") (pinfunction "1_1") (pintype "passive"))
      (node (ref "FR15") (pin "1") (pinfunction "1_1") (pintype "passive"))
    )
    (net (code "32") (name "Net-(C61-Pad1)") (class "Default")
      (node (ref "C61") (pin "1") (pinfunction "1_1") (pintype "passive"))
      (node (ref "FR20") (pin "2") (pinfunction "2_2") (pintype "passive"))
    )
    (net (code "33") (name "Net-(C62-Pad1)") (class "Default")
      (node (ref "C62") (pin "1") (pinfunction "1_1") (pintype "passive"))
      (node (ref "FR21") (pin "2") (pinfunction "2_2") (pintype "passive"))
    )
    (net (code "34") (name "Net-(C63-Pad1)") (class "Default")
      (node (ref "C63") (pin "1") (pinfunction "1_1") (pintype "passive"))
      (node (ref "FR19") (pin "1") (pinfunction "1_1") (pintype "passive"))
    )
    (net (code "35") (name "Net-(C64-Pad1)") (class "Default")
      (node (ref "C64") (pin "1") (pinfunction "1_1") (pintype "passive"))
      (node (ref "R32") (pin "2") (pinfunction "2_2") (pintype "passive"))
    )
    (net (code "36") (name "Net-(C65-Pad1)") (class "Default")
      (node (ref "C65") (pin "1") (pinfunction "1_1") (pintype "passive"))
      (node (ref "FR20") (pin "1") (pinfunction "1_1") (pintype "passive"))
      (node (ref "R33") (pin "1") (pinfunction "1_1") (pintype "passive"))
    )
    (net (code "37") (name "Net-(C66-Pad1)") (class "Default")
      (node (ref "C66") (pin "1") (pinfunction "1_1") (pintype "passive"))
      (node (ref "FR22") (pin "1") (pinfunction "1_1") (pintype "passive"))
    )
    (net (code "38") (name "Net-(C67-Pad1)") (class "Default")
      (node (ref "C67") (pin "1") (pinfunction "1_1") (pintype "passive"))
      (node (ref "FR27") (pin "2") (pinfunction "2_2") (pintype "passive"))
    )
    (net (code "39") (name "Net-(C68-Pad1)") (class "Default")
      (node (ref "C68") (pin "1") (pinfunction "1_1") (pintype "passive"))
      (node (ref "FR23") (pin "2") (pinfunction "2_2") (pintype "passive"))
    )
    (net (code "40") (name "Net-(C69-Pad1)") (class "Default")
      (node (ref "C69") (pin "1") (pinfunction "1_1") (pintype "passive"))
      (node (ref "FR24") (pin "1") (pinfunction "1_1") (pintype "passive"))
      (node (ref "FR25") (pin "1") (pinfunction "1_1") (pintype "passive"))
    )
    (net (code "41") (name "Net-(C70-Pad1)") (class "Default")
      (node (ref "C70") (pin "1") (pinfunction "1_1") (pintype "passive"))
      (node (ref "FR26") (pin "1") (pinfunction "1_1") (pintype "passive"))
    )
    (net (code "42") (name "Net-(C71-Pad1)") (class "Default")
      (node (ref "C71") (pin "1") (pinfunction "1_1") (pintype "passive"))
      (node (ref "FR28") (pin "2") (pinfunction "2_2") (pintype "passive"))
    )
    (net (code "43") (name "Net-(C72-Pad1)") (class "Default")
      (node (ref "C72") (pin "1") (pinfunction "1_1") (pintype "passive"))
      (node (ref "FR30") (pin "2") (pinfunction "2_2") (pintype "passive"))
    )
    (net (code "44") (name "Net-(C73-Pad1)") (class "Default")
      (node (ref "C73") (pin "1") (pinfunction "1_1") (pintype "passive"))
      (node (ref "FR29") (pin "1") (pinfunction "1_1") (pintype "passive"))
    )
    (net (code "45") (name "Net-(C74-Pad1)") (class "Default")
      (node (ref "C74") (pin "1") (pinfunction "1_1") (pintype "passive"))
      (node (ref "FR29") (pin "2") (pinfunction "2_2") (pintype "passive"))
      (node (ref "R34") (pin "2") (pinfunction "2_2") (pintype "passive"))
    )
    (net (code "46") (name "Net-(C75-Pad1)") (class "Default")
      (node (ref "C75") (pin "1") (pinfunction "1_1") (pintype "passive"))
      (node (ref "FR31") (pin "1") (pinfunction "1_1") (pintype "passive"))
    )
    (net (code "47") (name "Net-(C76-Pad1)") (class "Default")
      (node (ref "C76") (pin "1") (pinfunction "1_1") (pintype "passive"))
      (node (ref "FR31") (pin "2") (pinfunction "2_2") (pintype "passive"))
      (node (ref "R35") (pin "2") (pinfunction "2_2") (pintype "passive"))
    )
    (net (code "48") (name "Net-(C77-Pad1)") (class "Default")
      (node (ref "C77") (pin "1") (pinfunction "1_1") (pintype "passive"))
      (node (ref "FR32") (pin "1") (pinfunction "1_1") (pintype "passive"))
    )
    (net (code "49") (name "Net-(C78-Pad1)") (class "Default")
      (node (ref "C78") (pin "1") (pinfunction "1_1") (pintype "passive"))
      (node (ref "FR33") (pin "1") (pinfunction "1_1") (pintype "passive"))
    )
    (net (code "50") (name "Net-(C79-Pad1)") (class "Default")
      (node (ref "C79") (pin "1") (pinfunction "1_1") (pintype "passive"))
      (node (ref "FR34") (pin "1") (pinfunction "1_1") (pintype "passive"))
    )
    (net (code "51") (name "Net-(C80-Pad1)") (class "Default")
      (node (ref "C80") (pin "1") (pinfunction "1_1") (pintype "passive"))
      (node (ref "FR35") (pin "1") (pinfunction "1_1") (pintype "passive"))
    )
    (net (code "52") (name "VCC1P4_LMS") (class "Default")
      (node (ref "FR16") (pin "1") (pinfunction "1_1") (pintype "passive"))
      (node (ref "FR17") (pin "2") (pinfunction "2_2") (pintype "passive"))
      (node (ref "FR24") (pin "2") (pinfunction "2_2") (pintype "passive"))
      (node (ref "FR33") (pin "2") (pinfunction "2_2") (pintype "passive"))
      (node (ref "FR34") (pin "2") (pinfunction "2_2") (pintype "passive"))
      (node (ref "FR35") (pin "2") (pinfunction "2_2") (pintype "passive"))
    )
    (net (code "53") (name "VCC1P8_LMS") (class "Default")
      (node (ref "FR12") (pin "2") (pinfunction "2_2") (pintype "passive"))
      (node (ref "FR19") (pin "2") (pinfunction "2_2") (pintype "passive"))
      (node (ref "FR21") (pin "1") (pinfunction "1_1") (pintype "passive"))
      (node (ref "FR23") (pin "1") (pinfunction "1_1") (pintype "passive"))
      (node (ref "FR3") (pin "2") (pinfunction "2_2") (pintype "passive"))
      (node (ref "FR32") (pin "2") (pinfunction "2_2") (pintype "passive"))
      (node (ref "FR6") (pin "2") (pinfunction "2_2") (pintype "passive"))
      (node (ref "FR7") (pin "2") (pinfunction "2_2") (pintype "passive"))
      (node (ref "R25") (pin "2") (pinfunction "2_2") (pintype "passive"))
      (node (ref "R27") (pin "2") (pinfunction "2_2") (pintype "passive"))
      (node (ref "R35") (pin "1") (pinfunction "1_1") (pintype "passive"))
    )
    (net (code "54") (name "VCC1P25_LMS") (class "Default")
      (node (ref "FR1") (pin "2") (pinfunction "2_2") (pintype "passive"))
      (node (ref "FR11") (pin "2") (pinfunction "2_2") (pintype "passive"))
      (node (ref "FR13") (pin "2") (pinfunction "2_2") (pintype "passive"))
      (node (ref "FR14") (pin "1") (pinfunction "1_1") (pintype "passive"))
      (node (ref "FR15") (pin "2") (pinfunction "2_2") (pintype "passive"))
      (node (ref "FR18") (pin "1") (pinfunction "1_1") (pintype "passive"))
      (node (ref "FR2") (pin "1") (pinfunction "1_1") (pintype "passive"))
      (node (ref "FR22") (pin "2") (pinfunction "2_2") (pintype "passive"))
      (node (ref "FR25") (pin "2") (pinfunction "2_2") (pintype "passive"))
      (node (ref "FR26") (pin "2") (pinfunction "2_2") (pintype "passive"))
      (node (ref "FR27") (pin "1") (pinfunction "1_1") (pintype "passive"))
      (node (ref "FR28") (pin "1") (pinfunction "1_1") (pintype "passive"))
      (node (ref "FR30") (pin "1") (pinfunction "1_1") (pintype "passive"))
      (node (ref "FR4") (pin "1") (pinfunction "1_1") (pintype "passive"))
      (node (ref "FR5") (pin "1") (pinfunction "1_1") (pintype "passive"))
      (node (ref "FR8") (pin "2") (pinfunction "2_2") (pintype "passive"))
      (node (ref "FR9") (pin "1") (pinfunction "1_1") (pintype "passive"))
      (node (ref "R29") (pin "1") (pinfunction "1_1") (pintype "passive"))
      (node (ref "R30") (pin "2") (pinfunction "2_2") (pintype "passive"))
      (node (ref "R32") (pin "1") (pinfunction "1_1") (pintype "passive"))
      (node (ref "R33") (pin "2") (pinfunction "2_2") (pintype "passive"))
      (node (ref "R34") (pin "1") (pinfunction "1_1") (pintype "passive"))
    )
    (net (code "55") (name "VCC1P25_LMS_DIG") (class "Default")
      (node (ref "R16") (pin "2") (pinfunction "2_2") (pintype "passive"))
      (node (ref "R18") (pin "2") (pinfunction "2_2") (pintype "passive"))
      (node (ref "R20") (pin "2") (pinfunction "2_2") (pintype "passive"))
      (node (ref "R22") (pin "2") (pinfunction "2_2") (pintype "passive"))
    )
    (net (code "56") (name "VDIO_LMS") (class "Default")
      (node (ref "R17") (pin "1") (pinfunction "1_1") (pintype "passive"))
      (node (ref "R19") (pin "1") (pinfunction "1_1") (pintype "passive"))
      (node (ref "R21") (pin "1") (pinfunction "1_1") (pintype "passive"))
      (node (ref "R23") (pin "1") (pinfunction "1_1") (pintype "passive"))
      (node (ref "R24") (pin "1") (pinfunction "1_1") (pintype "passive"))
    )
    (net (code "57") (name "unconnected-(R26-Pad2)") (class "Default")
      (node (ref "R26") (pin "2") (pinfunction "2_2") (pintype "passive"))
    )
    (net (code "58") (name "unconnected-(R28-Pad1)") (class "Default")
      (node (ref "R28") (pin "1") (pinfunction "1_1") (pintype "passive"))
    )
    (net (code "59") (name "unconnected-(R31-Pad1)") (class "Default")
      (node (ref "R31") (pin "1") (pinfunction "1_1") (pintype "passive"))
    )
  )
)
